# Transducer.net
KiCad netlist of a schematic drawn in Altium Designer
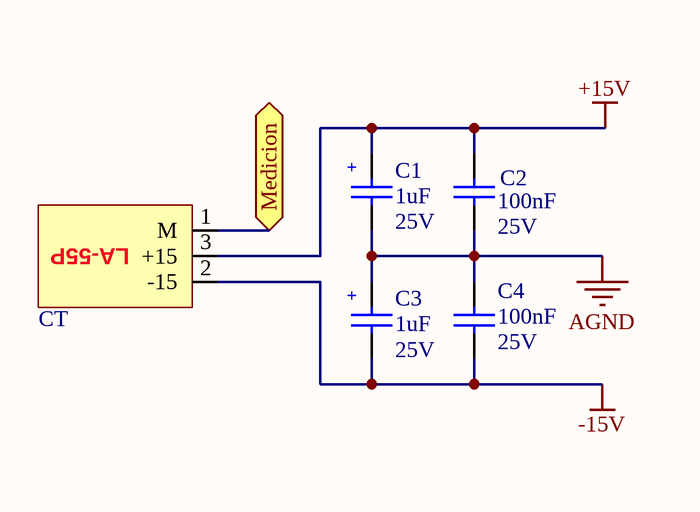
[diagram p0: Transducer.SchDoc]

(export (version "E")
  (design (tool "Eeschema 10.0.6"))
  (components
    (comp (ref "C1")
      (value "1uF")
      (footprint "CAP_1206 Tantalio")
      (description "Capacitor Tantalio")
      (fields (field (name "VOLTAGE") "25V"))
      (libsource (lib "Componentes_SOC") (part "Cap Tantalio 1206"))
    )
    (comp (ref "C2")
      (value "100nF")
      (footprint "CAP_0805")
      (description "Capacitor")
      (fields (field (name "VOLTAGE") "25V"))
      (libsource (lib "Componentes_SOC") (part "Cap_0805"))
    )
    (comp (ref "C3")
      (value "1uF")
      (footprint "CAP_1206 Tantalio")
      (description "Capacitor Tantalio")
      (fields (field (name "VOLTAGE") "25V"))
      (libsource (lib "Componentes_SOC") (part "Cap Tantalio 1206"))
    )
    (comp (ref "C4")
      (value "100nF")
      (footprint "CAP_0805")
      (description "Capacitor")
      (fields (field (name "VOLTAGE") "25V"))
      (libsource (lib "Componentes_SOC") (part "Cap_0805"))
    )
    (comp (ref "CT")
      (value "Current Sensor 50A 1 Channel Hall Effect, Closed Loop Bidirectional Module")
      (footprint "LEM_LA 55-P")
      (description "LA 55-P")
      (fields (field (name "MANUFACTURER") "LEM USA Inc."))
      (libsource (lib "Componentes_SOC") (part "LEM_LA 55-P"))
    )
  )
  (nets
    (net (code "1") (name "+15V") (class "Default")
      (node (ref "C1") (pin "1") (pinfunction "1_1") (pintype "passive"))
      (node (ref "C2") (pin "1") (pinfunction "1_1") (pintype "passive"))
      (node (ref "CT") (pin "3") (pinfunction "+15_3") (pintype "passive"))
    )
    (net (code "2") (name "-15V") (class "Default")
      (node (ref "C3") (pin "2") (pinfunction "2_2") (pintype "passive"))
      (node (ref "C4") (pin "2") (pinfunction "2_2") (pintype "passive"))
      (node (ref "CT") (pin "2") (pinfunction "-15_2") (pintype "passive"))
    )
    (net (code "3") (name "/Medicion") (class "Default")
      (node (ref "CT") (pin "1") (pinfunction "M_1") (pintype "passive"))
    )
    (net (code "4") (name "AGND") (class "Default")
      (node (ref "C1") (pin "2") (pinfunction "2_2") (pintype "passive"))
      (node (ref "C2") (pin "2") (pinfunction "2_2") (pintype "passive"))
      (node (ref "C3") (pin "1") (pinfunction "1_1") (pintype "passive"))
      (node (ref "C4") (pin "1") (pinfunction "1_1") (pintype "passive"))
    )
  )
)
